# SCH_GSME_voltmeter_Arduino_ESP8266_TP405.net
KiCad netlist of a schematic drawn in EasyEDA
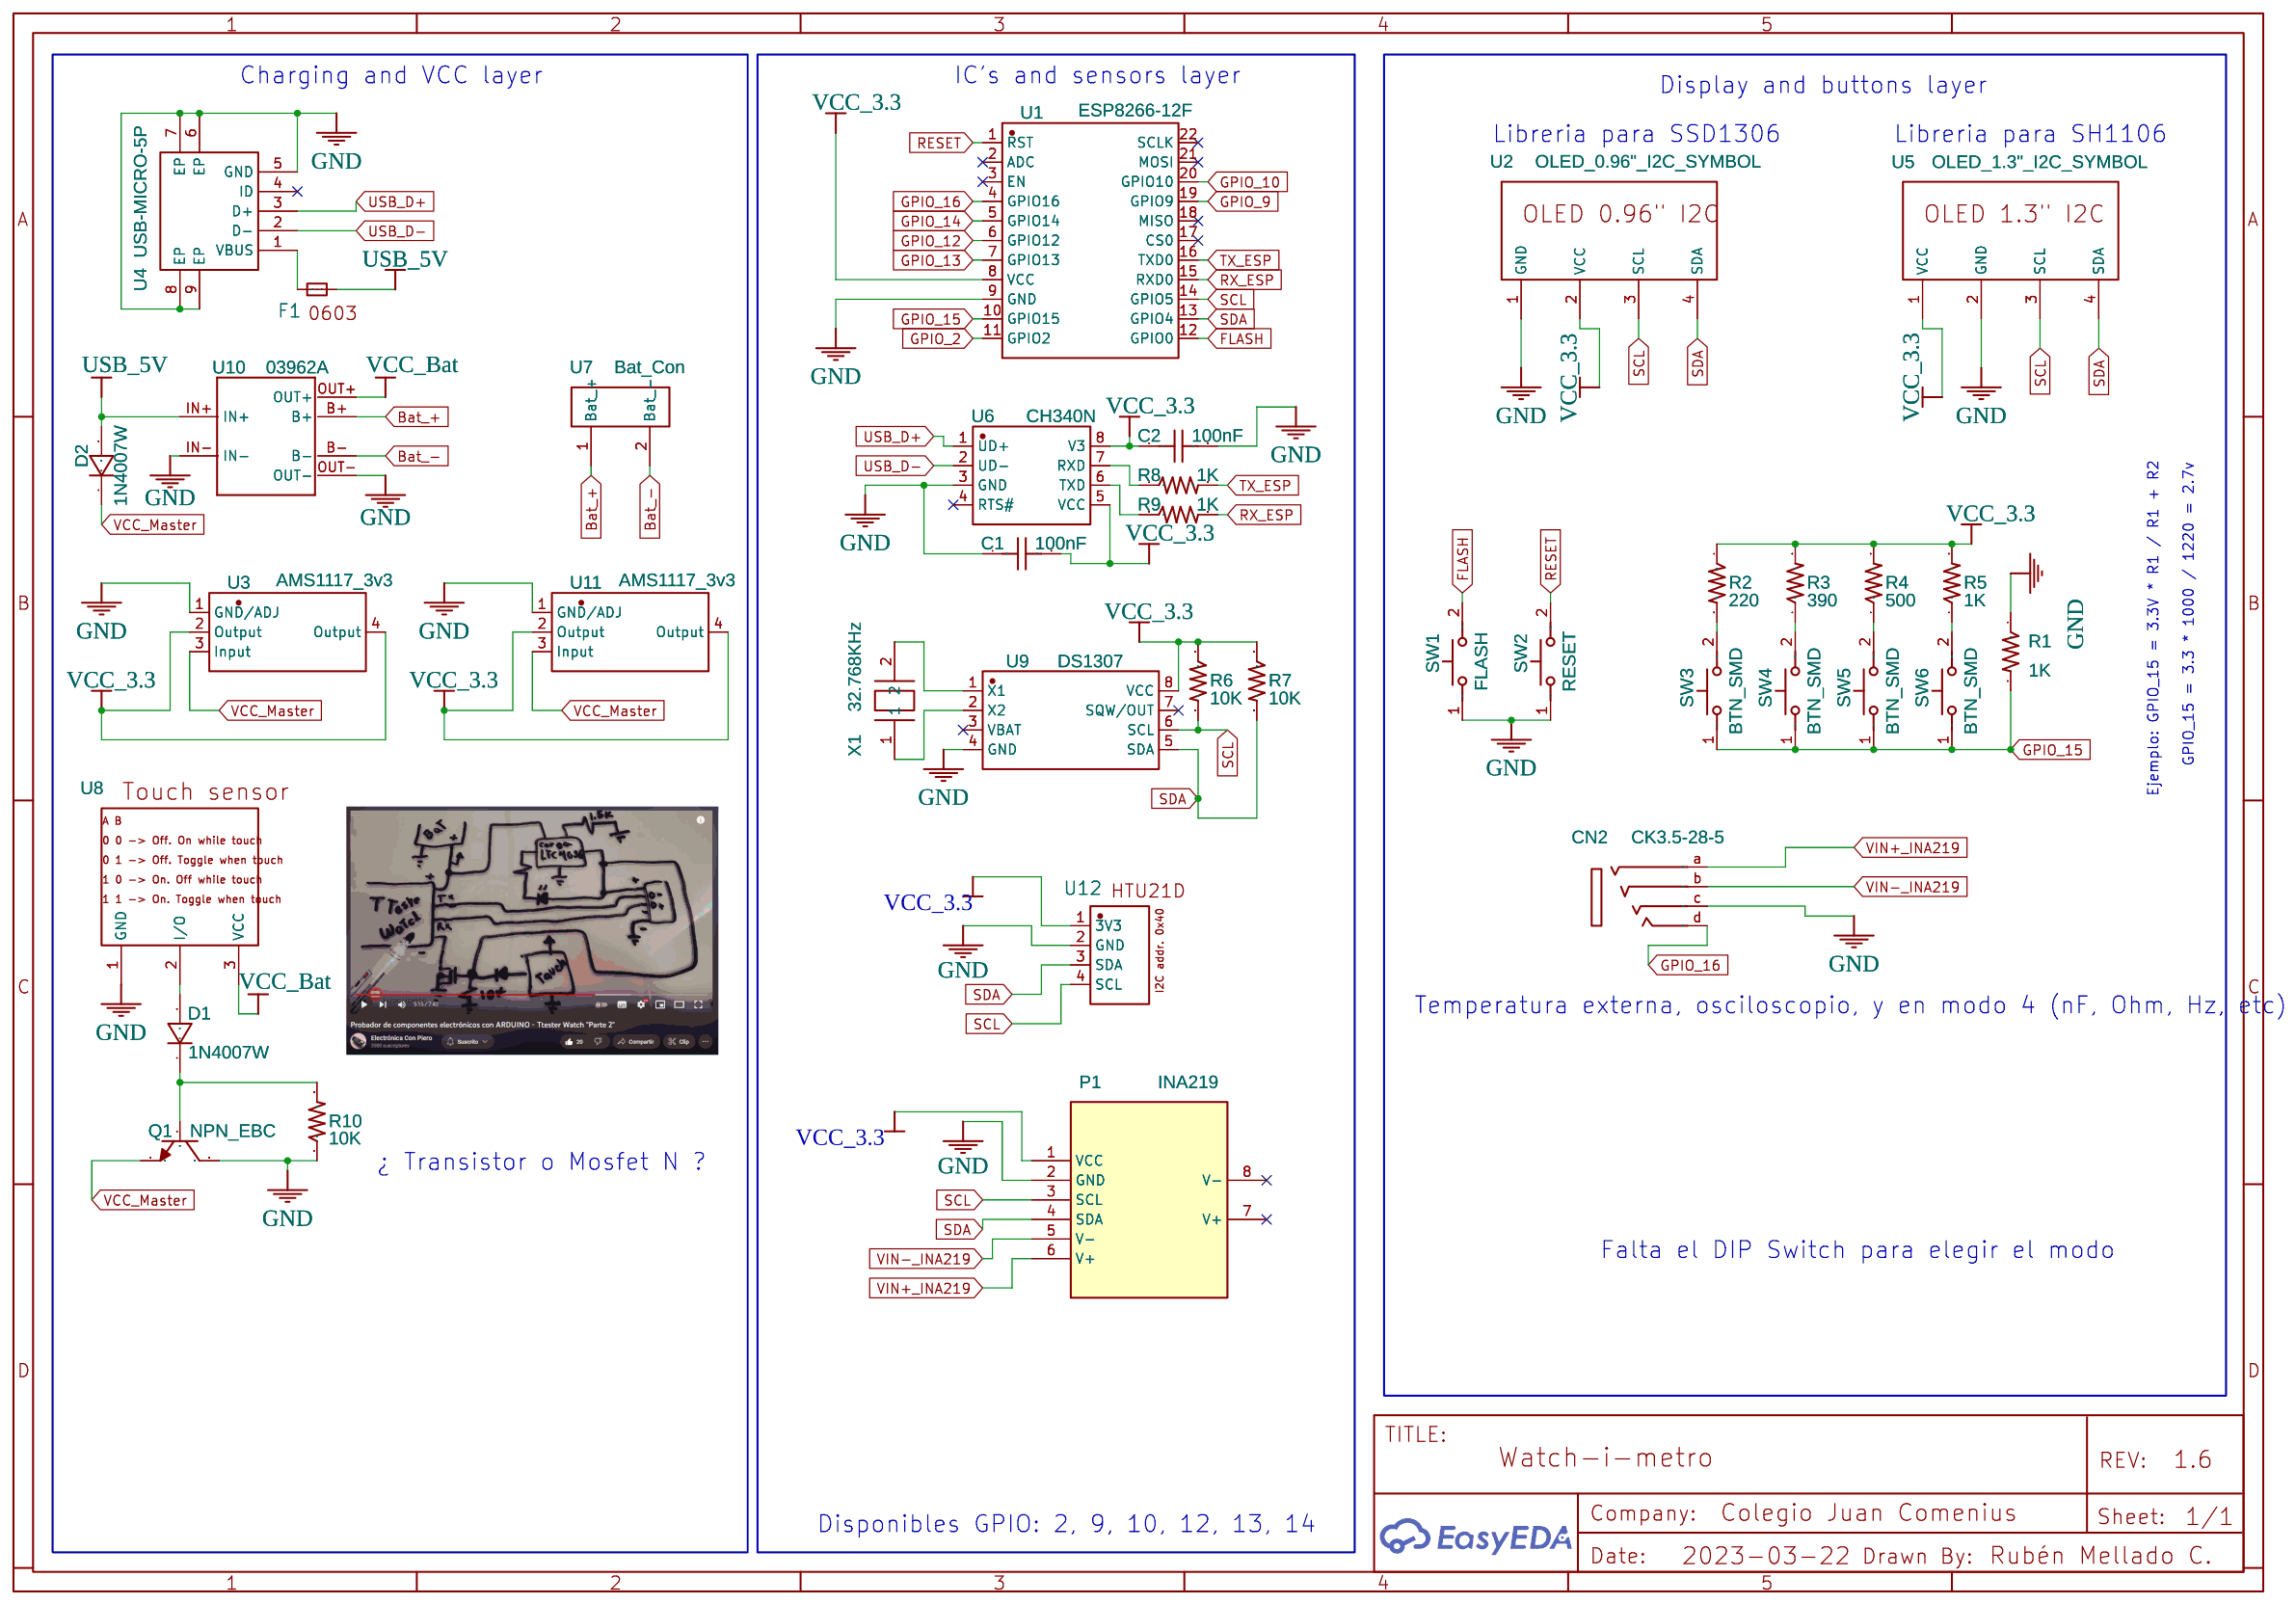
[diagram p0: schematic sheet]

(export (version "E")
  (design (tool "Eeschema 10.0.6"))
  (components
    (comp (ref "C1") (value "100nF") (libsource (lib "") (part "C_0603_US")))
    (comp (ref "C2") (value "100nF") (libsource (lib "") (part "C_0603_US")))
    (comp (ref "CN2")
      (value "CK3.5-28-5")
      (fields (field (name "BOM_Supplier Part") "C718048"))
      (libsource (lib "") (part "CK3.5-28-5"))
    )
    (comp (ref "D1")
      (value "1N4007W")
      (fields (field (name "BOM_Supplier Part") "C328592"))
      (libsource (lib "") (part "1N4007W"))
    )
    (comp (ref "D2")
      (value "1N4007W")
      (fields (field (name "BOM_Supplier Part") "C328592"))
      (libsource (lib "") (part "1N4007W"))
    )
    (comp (ref "F1")
      (value "Fuse")
      (fields (field (name "BOM_Manufacturer Part") "0603") (field (name "BOM_Supplier Part") "C9900014602"))
      (libsource (lib "") (part "0603_FUSE_SYMBOL"))
    )
    (comp (ref "P1") (value "INA219") (libsource (lib "") (part "INA219")))
    (comp (ref "Q1")
      (value "NPN_EBC")
      (fields
        (field (name "BOM_Manufacturer Part") "2n3904S-RTK/PS")
        (field (name "BOM_Supplier Part") "C18536")
      )
      (libsource (lib "") (part "2N3904(SOT-23)"))
    )
    (comp (ref "R1") (value "1K") (libsource (lib "") (part "RESISTOR0603_1")))
    (comp (ref "R2") (value "220") (libsource (lib "") (part "RESISTOR0603_1")))
    (comp (ref "R3") (value "390") (libsource (lib "") (part "RESISTOR0603")))
    (comp (ref "R4") (value "500") (libsource (lib "") (part "RESISTOR0603")))
    (comp (ref "R5") (value "1K") (libsource (lib "") (part "RESISTOR0603")))
    (comp (ref "R6") (value "10K") (libsource (lib "") (part "RESISTOR0603_1")))
    (comp (ref "R7") (value "10K") (libsource (lib "") (part "RESISTOR0603_1")))
    (comp (ref "R8") (value "1K") (libsource (lib "") (part "RESISTOR0603_2")))
    (comp (ref "R9") (value "1K") (libsource (lib "") (part "RESISTOR0603_2")))
    (comp (ref "R10") (value "10K") (libsource (lib "") (part "RESISTOR0603")))
    (comp (ref "SW1")
      (value "FLASH")
      (fields
        (field (name "BOM_Manufacturer Part") "BUTTON2")
        (field (name "BOM_Supplier Part") "C9900005988")
      )
      (libsource (lib "") (part "BUTTON2"))
    )
    (comp (ref "SW2")
      (value "RESET")
      (fields
        (field (name "BOM_Manufacturer Part") "BUTTON2")
        (field (name "BOM_Supplier Part") "C9900005988")
      )
      (libsource (lib "") (part "BUTTON2"))
    )
    (comp (ref "SW3")
      (value "BTN_SMD")
      (fields
        (field (name "BOM_Manufacturer Part") "BUTTON2")
        (field (name "BOM_Supplier Part") "C9900005988")
      )
      (libsource (lib "") (part "BUTTON2"))
    )
    (comp (ref "SW4")
      (value "BTN_SMD")
      (fields
        (field (name "BOM_Manufacturer Part") "BUTTON2")
        (field (name "BOM_Supplier Part") "C9900005988")
      )
      (libsource (lib "") (part "BUTTON2"))
    )
    (comp (ref "SW5")
      (value "BTN_SMD")
      (fields
        (field (name "BOM_Manufacturer Part") "BUTTON2")
        (field (name "BOM_Supplier Part") "C9900005988")
      )
      (libsource (lib "") (part "BUTTON2"))
    )
    (comp (ref "SW6")
      (value "BTN_SMD")
      (fields
        (field (name "BOM_Manufacturer Part") "BUTTON2")
        (field (name "BOM_Supplier Part") "C9900005988")
      )
      (libsource (lib "") (part "BUTTON2"))
    )
    (comp (ref "U1")
      (value "ESP8266-12F")
      (fields
        (field (name "BOM_Manufacturer Part") "ESP-12F(ESP8266MOD)")
        (field (name "BOM_Supplier Part") "C82891")
      )
      (libsource (lib "") (part "ESP-12F(ESP8266MOD)"))
    )
    (comp (ref "U2")
      (value "OLED_0.96\"_I2C_SYMBOL")
      (libsource (lib "") (part "OLED_0.96{dblquote}_I2C_SYMBOL"))
    )
    (comp (ref "U3")
      (value "AMS1117_3v3")
      (fields
        (field (name "BOM_Manufacturer Part") "AMS1117-3.3S")
        (field (name "BOM_Supplier Part") "C2842296")
      )
      (libsource (lib "") (part "AMS1117-3.3S"))
    )
    (comp (ref "U4")
      (value "USB-MICRO-5P")
      (fields
        (field (name "BOM_Manufacturer Part") "USB-Micro-5P")
        (field (name "BOM_Supplier Part") "C9900014288")
      )
      (libsource (lib "") (part "USB-MICRO-5P"))
    )
    (comp (ref "U5")
      (value "OLED_1.3\"_I2C_SYMBOL")
      (libsource (lib "") (part "OLED_1.3{dblquote}_I2C_SYMBOL"))
    )
    (comp (ref "U6")
      (value "CH340N")
      (fields (field (name "BOM_Supplier Part") "C506813"))
      (libsource (lib "") (part "CH340N"))
    )
    (comp (ref "U7") (value "Bat_Con") (libsource (lib "") (part "Connector_Battery_2_Wires_2p")))
    (comp (ref "U8") (value "Touch_Sensor") (libsource (lib "") (part "Touch_Sensor_3p_A_B_SYMBOL")))
    (comp (ref "U9")
      (value "DS1307")
      (fields
        (field (name "BOM_Manufacturer Part") "DS1307M/TR")
        (field (name "BOM_Supplier Part") "C356706")
      )
      (libsource (lib "") (part "DS1307M/TR"))
    )
    (comp (ref "U10") (value "03962A") (libsource (lib "") (part "03962A")))
    (comp (ref "U11")
      (value "AMS1117_3v3")
      (fields
        (field (name "BOM_Manufacturer Part") "AMS1117-3.3S")
        (field (name "BOM_Supplier Part") "C2842296")
      )
      (libsource (lib "") (part "AMS1117-3.3S"))
    )
    (comp (ref "U12") (value "HTU21D") (libsource (lib "") (part "SF HTU21D HUMIDITY")))
    (comp (ref "X1") (value "32.768KHz") (libsource (lib "") (part "Quartz_X_2p_Symbol")))
  )
  (nets
    (net (code "1") (name "Bat_+") (class "Default")
      (node (ref "U10") (pin "B+") (pinfunction "B+_B+") (pintype "bidirectional"))
      (node (ref "U7") (pin "1") (pinfunction "Bat_+_1") (pintype "unspecified"))
    )
    (net (code "2") (name "Bat_-") (class "Default")
      (node (ref "U10") (pin "B-") (pinfunction "B-_B-") (pintype "bidirectional"))
      (node (ref "U7") (pin "2") (pinfunction "Bat_-_2") (pintype "unspecified"))
    )
    (net (code "3") (name "FLASH") (class "Default")
      (node (ref "SW1") (pin "2") (pinfunction "2_2") (pintype "unspecified"))
      (node (ref "U1") (pin "12") (pinfunction "GPIO0_12") (pintype "unspecified"))
    )
    (net (code "4") (name "GND") (class "Default")
      (node (ref "C1") (pin "1") (pinfunction "1_1") (pintype "unspecified"))
      (node (ref "C2") (pin "2") (pinfunction "2_2") (pintype "unspecified"))
      (node (ref "CN2") (pin "c") (pinfunction "c_c") (pintype "unspecified"))
      (node (ref "P1") (pin "2") (pinfunction "GND_2") (pintype "unspecified"))
      (node (ref "Q1") (pin "2") (pinfunction "C_2") (pintype "input"))
      (node (ref "R1") (pin "1") (pinfunction "1_1") (pintype "unspecified"))
      (node (ref "R10") (pin "1") (pinfunction "1_1") (pintype "unspecified"))
      (node (ref "SW1") (pin "1") (pinfunction "1_1") (pintype "unspecified"))
      (node (ref "SW2") (pin "1") (pinfunction "1_1") (pintype "unspecified"))
      (node (ref "U1") (pin "9") (pinfunction "GND_9") (pintype "unspecified"))
      (node (ref "U10") (pin "IN-") (pinfunction "IN-_IN-") (pintype "bidirectional"))
      (node (ref "U10") (pin "OUT-") (pinfunction "OUT-_OUT-") (pintype "bidirectional"))
      (node (ref "U11") (pin "1") (pinfunction "GND/ADJ_1") (pintype "unspecified"))
      (node (ref "U12") (pin "2") (pinfunction "GND_2") (pintype "unspecified"))
      (node (ref "U2") (pin "1") (pinfunction "GND_1") (pintype "unspecified"))
      (node (ref "U3") (pin "1") (pinfunction "GND/ADJ_1") (pintype "unspecified"))
      (node (ref "U4") (pin "5") (pinfunction "GND_5") (pintype "unspecified"))
      (node (ref "U4") (pin "6") (pinfunction "EP_6") (pintype "unspecified"))
      (node (ref "U4") (pin "7") (pinfunction "EP_7") (pintype "unspecified"))
      (node (ref "U4") (pin "8") (pinfunction "EP_8") (pintype "unspecified"))
      (node (ref "U4") (pin "9") (pinfunction "EP_9") (pintype "unspecified"))
      (node (ref "U5") (pin "2") (pinfunction "GND_2") (pintype "unspecified"))
      (node (ref "U6") (pin "3") (pinfunction "GND_3") (pintype "unspecified"))
      (node (ref "U8") (pin "1") (pinfunction "GND_1") (pintype "unspecified"))
      (node (ref "U9") (pin "4") (pinfunction "GND_4") (pintype "unspecified"))
    )
    (net (code "5") (name "GPIO_2") (class "Default")
      (node (ref "U1") (pin "11") (pinfunction "GPIO2_11") (pintype "unspecified"))
    )
    (net (code "6") (name "GPIO_9") (class "Default")
      (node (ref "U1") (pin "19") (pinfunction "GPIO9_19") (pintype "unspecified"))
    )
    (net (code "7") (name "GPIO_10") (class "Default")
      (node (ref "U1") (pin "20") (pinfunction "GPIO10_20") (pintype "unspecified"))
    )
    (net (code "8") (name "GPIO_12") (class "Default")
      (node (ref "U1") (pin "6") (pinfunction "GPIO12_6") (pintype "unspecified"))
    )
    (net (code "9") (name "GPIO_13") (class "Default")
      (node (ref "U1") (pin "7") (pinfunction "GPIO13_7") (pintype "unspecified"))
    )
    (net (code "10") (name "GPIO_14") (class "Default")
      (node (ref "U1") (pin "5") (pinfunction "GPIO14_5") (pintype "unspecified"))
    )
    (net (code "11") (name "GPIO_15") (class "Default")
      (node (ref "R1") (pin "2") (pinfunction "2_2") (pintype "unspecified"))
      (node (ref "SW3") (pin "1") (pinfunction "1_1") (pintype "unspecified"))
      (node (ref "SW4") (pin "1") (pinfunction "1_1") (pintype "unspecified"))
      (node (ref "SW5") (pin "1") (pinfunction "1_1") (pintype "unspecified"))
      (node (ref "SW6") (pin "1") (pinfunction "1_1") (pintype "unspecified"))
      (node (ref "U1") (pin "10") (pinfunction "GPIO15_10") (pintype "unspecified"))
    )
    (net (code "12") (name "GPIO_16") (class "Default")
      (node (ref "CN2") (pin "d") (pinfunction "d_d") (pintype "unspecified"))
      (node (ref "U1") (pin "4") (pinfunction "GPIO16_4") (pintype "unspecified"))
    )
    (net (code "13") (name "Net-(F1-K)") (class "Default")
      (node (ref "F1") (pin "1") (pinfunction "K_1") (pintype "unspecified"))
      (node (ref "U4") (pin "1") (pinfunction "VBUS_1") (pintype "unspecified"))
    )
    (net (code "14") (name "Net-(Q1-B)") (class "Default")
      (node (ref "D1") (pin "1") (pinfunction "1_1") (pintype "unspecified"))
      (node (ref "Q1") (pin "3") (pinfunction "B_3") (pintype "input"))
      (node (ref "R10") (pin "2") (pinfunction "2_2") (pintype "unspecified"))
    )
    (net (code "15") (name "Net-(R2-Pad2)") (class "Default")
      (node (ref "R2") (pin "2") (pinfunction "2_2") (pintype "unspecified"))
      (node (ref "SW3") (pin "2") (pinfunction "2_2") (pintype "unspecified"))
    )
    (net (code "16") (name "Net-(R3-Pad1)") (class "Default")
      (node (ref "R3") (pin "1") (pinfunction "1_1") (pintype "unspecified"))
      (node (ref "SW4") (pin "2") (pinfunction "2_2") (pintype "unspecified"))
    )
    (net (code "17") (name "Net-(R4-Pad1)") (class "Default")
      (node (ref "R4") (pin "1") (pinfunction "1_1") (pintype "unspecified"))
      (node (ref "SW5") (pin "2") (pinfunction "2_2") (pintype "unspecified"))
    )
    (net (code "18") (name "Net-(R5-Pad1)") (class "Default")
      (node (ref "R5") (pin "1") (pinfunction "1_1") (pintype "unspecified"))
      (node (ref "SW6") (pin "2") (pinfunction "2_2") (pintype "unspecified"))
    )
    (net (code "19") (name "Net-(U6-RXD)") (class "Default")
      (node (ref "R8") (pin "1") (pinfunction "1_1") (pintype "unspecified"))
      (node (ref "U6") (pin "7") (pinfunction "RXD_7") (pintype "unspecified"))
    )
    (net (code "20") (name "Net-(U6-TXD)") (class "Default")
      (node (ref "R9") (pin "1") (pinfunction "1_1") (pintype "unspecified"))
      (node (ref "U6") (pin "6") (pinfunction "TXD_6") (pintype "unspecified"))
    )
    (net (code "21") (name "Net-(U8-I{slash}O)") (class "Default")
      (node (ref "D1") (pin "2") (pinfunction "2_2") (pintype "unspecified"))
      (node (ref "U8") (pin "2") (pinfunction "I/O_2") (pintype "unspecified"))
    )
    (net (code "22") (name "Net-(U9-X1)") (class "Default")
      (node (ref "U9") (pin "1") (pinfunction "X1_1") (pintype "unspecified"))
      (node (ref "X1") (pin "2") (pinfunction "2_2") (pintype "unspecified"))
    )
    (net (code "23") (name "Net-(U9-X2)") (class "Default")
      (node (ref "U9") (pin "2") (pinfunction "X2_2") (pintype "unspecified"))
      (node (ref "X1") (pin "1") (pinfunction "1_1") (pintype "unspecified"))
    )
    (net (code "24") (name "RESET") (class "Default")
      (node (ref "SW2") (pin "2") (pinfunction "2_2") (pintype "unspecified"))
      (node (ref "U1") (pin "1") (pinfunction "RST_1") (pintype "unspecified"))
    )
    (net (code "25") (name "RX_ESP") (class "Default")
      (node (ref "R9") (pin "2") (pinfunction "2_2") (pintype "unspecified"))
      (node (ref "U1") (pin "15") (pinfunction "RXD0_15") (pintype "unspecified"))
    )
    (net (code "26") (name "SCL") (class "Default")
      (node (ref "P1") (pin "3") (pinfunction "SCL_3") (pintype "unspecified"))
      (node (ref "R6") (pin "2") (pinfunction "2_2") (pintype "unspecified"))
      (node (ref "U1") (pin "14") (pinfunction "GPIO5_14") (pintype "unspecified"))
      (node (ref "U12") (pin "4") (pinfunction "SCL_4") (pintype "unspecified"))
      (node (ref "U2") (pin "3") (pinfunction "SCL_3") (pintype "unspecified"))
      (node (ref "U5") (pin "3") (pinfunction "SCL_3") (pintype "unspecified"))
      (node (ref "U9") (pin "6") (pinfunction "SCL_6") (pintype "unspecified"))
    )
    (net (code "27") (name "SDA") (class "Default")
      (node (ref "P1") (pin "4") (pinfunction "SDA_4") (pintype "unspecified"))
      (node (ref "R7") (pin "2") (pinfunction "2_2") (pintype "unspecified"))
      (node (ref "U1") (pin "13") (pinfunction "GPIO4_13") (pintype "unspecified"))
      (node (ref "U12") (pin "3") (pinfunction "SDA_3") (pintype "unspecified"))
      (node (ref "U2") (pin "4") (pinfunction "SDA_4") (pintype "unspecified"))
      (node (ref "U5") (pin "4") (pinfunction "SDA_4") (pintype "unspecified"))
      (node (ref "U9") (pin "5") (pinfunction "SDA_5") (pintype "unspecified"))
    )
    (net (code "28") (name "TX_ESP") (class "Default")
      (node (ref "R8") (pin "2") (pinfunction "2_2") (pintype "unspecified"))
      (node (ref "U1") (pin "16") (pinfunction "TXD0_16") (pintype "unspecified"))
    )
    (net (code "29") (name "USB_5V") (class "Default")
      (node (ref "D2") (pin "2") (pinfunction "2_2") (pintype "unspecified"))
      (node (ref "F1") (pin "2") (pinfunction "A_2") (pintype "unspecified"))
      (node (ref "U10") (pin "IN+") (pinfunction "IN+_IN+") (pintype "bidirectional"))
    )
    (net (code "30") (name "USB_D+") (class "Default")
      (node (ref "U4") (pin "3") (pinfunction "D+_3") (pintype "unspecified"))
      (node (ref "U6") (pin "1") (pinfunction "UD+_1") (pintype "unspecified"))
    )
    (net (code "31") (name "USB_D-") (class "Default")
      (node (ref "U4") (pin "2") (pinfunction "D-_2") (pintype "unspecified"))
      (node (ref "U6") (pin "2") (pinfunction "UD-_2") (pintype "unspecified"))
    )
    (net (code "32") (name "VCC_3.3") (class "Default")
      (node (ref "C1") (pin "2") (pinfunction "2_2") (pintype "unspecified"))
      (node (ref "C2") (pin "1") (pinfunction "1_1") (pintype "unspecified"))
      (node (ref "P1") (pin "1") (pinfunction "VCC_1") (pintype "unspecified"))
      (node (ref "R2") (pin "1") (pinfunction "1_1") (pintype "unspecified"))
      (node (ref "R3") (pin "2") (pinfunction "2_2") (pintype "unspecified"))
      (node (ref "R4") (pin "2") (pinfunction "2_2") (pintype "unspecified"))
      (node (ref "R5") (pin "2") (pinfunction "2_2") (pintype "unspecified"))
      (node (ref "R6") (pin "1") (pinfunction "1_1") (pintype "unspecified"))
      (node (ref "R7") (pin "1") (pinfunction "1_1") (pintype "unspecified"))
      (node (ref "U1") (pin "8") (pinfunction "VCC_8") (pintype "unspecified"))
      (node (ref "U11") (pin "2") (pinfunction "Output_2") (pintype "unspecified"))
      (node (ref "U11") (pin "4") (pinfunction "Output_4") (pintype "unspecified"))
      (node (ref "U12") (pin "1") (pinfunction "3V3_1") (pintype "unspecified"))
      (node (ref "U2") (pin "2") (pinfunction "VCC_2") (pintype "unspecified"))
      (node (ref "U3") (pin "2") (pinfunction "Output_2") (pintype "unspecified"))
      (node (ref "U3") (pin "4") (pinfunction "Output_4") (pintype "unspecified"))
      (node (ref "U5") (pin "1") (pinfunction "VCC_1") (pintype "unspecified"))
      (node (ref "U6") (pin "5") (pinfunction "VCC_5") (pintype "unspecified"))
      (node (ref "U6") (pin "8") (pinfunction "V3_8") (pintype "unspecified"))
      (node (ref "U9") (pin "8") (pinfunction "VCC_8") (pintype "unspecified"))
    )
    (net (code "33") (name "VCC_Bat") (class "Default")
      (node (ref "U10") (pin "OUT+") (pinfunction "OUT+_OUT+") (pintype "bidirectional"))
      (node (ref "U8") (pin "3") (pinfunction "VCC_3") (pintype "unspecified"))
    )
    (net (code "34") (name "VCC_Master") (class "Default")
      (node (ref "D2") (pin "1") (pinfunction "1_1") (pintype "unspecified"))
      (node (ref "Q1") (pin "1") (pinfunction "E_1") (pintype "input"))
      (node (ref "U11") (pin "3") (pinfunction "Input_3") (pintype "unspecified"))
      (node (ref "U3") (pin "3") (pinfunction "Input_3") (pintype "unspecified"))
    )
    (net (code "35") (name "VIN+_INA219") (class "Default")
      (node (ref "CN2") (pin "a") (pinfunction "a_a") (pintype "unspecified"))
      (node (ref "P1") (pin "6") (pinfunction "V+_6") (pintype "unspecified"))
    )
    (net (code "36") (name "VIN-_INA219") (class "Default")
      (node (ref "CN2") (pin "b") (pinfunction "b_b") (pintype "unspecified"))
      (node (ref "P1") (pin "5") (pinfunction "V-_5") (pintype "unspecified"))
    )
    (net (code "37") (name "unconnected-(P1-V+-Pad7)") (class "Default")
      (node (ref "P1") (pin "7") (pinfunction "V+_7") (pintype "unspecified+no_connect"))
    )
    (net (code "38") (name "unconnected-(P1-V--Pad8)") (class "Default")
      (node (ref "P1") (pin "8") (pinfunction "V-_8") (pintype "unspecified+no_connect"))
    )
    (net (code "39") (name "unconnected-(U1-ADC-Pad2)") (class "Default")
      (node (ref "U1") (pin "2") (pinfunction "ADC_2") (pintype "unspecified+no_connect"))
    )
    (net (code "40") (name "unconnected-(U1-CS0-Pad17)") (class "Default")
      (node (ref "U1") (pin "17") (pinfunction "CS0_17") (pintype "unspecified+no_connect"))
    )
    (net (code "41") (name "unconnected-(U1-EN-Pad3)") (class "Default")
      (node (ref "U1") (pin "3") (pinfunction "EN_3") (pintype "unspecified+no_connect"))
    )
    (net (code "42") (name "unconnected-(U1-MISO-Pad18)") (class "Default")
      (node (ref "U1") (pin "18") (pinfunction "MISO_18") (pintype "unspecified+no_connect"))
    )
    (net (code "43") (name "unconnected-(U1-MOSI-Pad21)") (class "Default")
      (node (ref "U1") (pin "21") (pinfunction "MOSI_21") (pintype "unspecified+no_connect"))
    )
    (net (code "44") (name "unconnected-(U1-SCLK-Pad22)") (class "Default")
      (node (ref "U1") (pin "22") (pinfunction "SCLK_22") (pintype "unspecified+no_connect"))
    )
    (net (code "45") (name "unconnected-(U4-ID-Pad4)") (class "Default")
      (node (ref "U4") (pin "4") (pinfunction "ID_4") (pintype "unspecified+no_connect"))
    )
    (net (code "46") (name "unconnected-(U6-RTS#-Pad4)") (class "Default")
      (node (ref "U6") (pin "4") (pinfunction "RTS#_4") (pintype "unspecified+no_connect"))
    )
    (net (code "47") (name "unconnected-(U9-SQW{slash}OUT-Pad7)") (class "Default")
      (node (ref "U9") (pin "7") (pinfunction "SQW/OUT_7") (pintype "unspecified+no_connect"))
    )
    (net (code "48") (name "unconnected-(U9-VBAT-Pad3)") (class "Default")
      (node (ref "U9") (pin "3") (pinfunction "VBAT_3") (pintype "unspecified+no_connect"))
    )
  )
)
